# Comparator_HighSpeed.net
KiCad netlist of a schematic drawn in Altium Designer
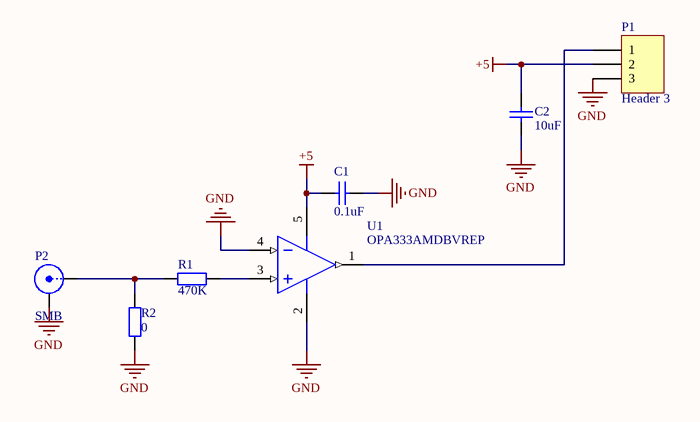
[diagram p0: Comparator_HighSpeed.SchDoc]

(export (version "E")
  (design (tool "Eeschema 10.0.6"))
  (components
    (comp (ref "C1")
      (value "0.1uF")
      (footprint "C0805")
      (description "Capacitor (Semiconductor SIM Model)")
      (fields (field (name "Comment") "Cap Semi") (field (name "PUBLISHER") "Altium Limited"))
      (libsource (lib "Miscellaneous Devices") (part "Cap Semi"))
    )
    (comp (ref "C2")
      (value "10uF")
      (footprint "C0805")
      (description "Capacitor (Semiconductor SIM Model)")
      (fields (field (name "Comment") "Cap Semi") (field (name "PUBLISHER") "Altium Limited"))
      (libsource (lib "Miscellaneous Devices") (part "Cap Semi"))
    )
    (comp (ref "P1")
      (value "Header 3")
      (footprint "HDR1X3")
      (description "Header, 3-Pin")
      (fields (field (name "PUBLISHER") "Altium Limited"))
      (libsource (lib "Miscellaneous Connectors") (part "Header 3"))
    )
    (comp (ref "P2")
      (value "SMB")
      (footprint "SMB_V-RJ45")
      (description "SMB Straight Connector")
      (fields (field (name "PUBLISHER") "Altium Limited"))
      (libsource (lib "Miscellaneous Connectors") (part "SMB"))
    )
    (comp (ref "R1")
      (value "470K")
      (footprint "C0805")
      (description "Resistor")
      (fields (field (name "Comment") "Res2") (field (name "PUBLISHER") "Altium Limited"))
      (libsource (lib "") (part "Res2_1"))
    )
    (comp (ref "R2")
      (value "0")
      (footprint "C0805")
      (description "Resistor")
      (fields (field (name "Comment") "Res2") (field (name "PUBLISHER") "Altium Limited"))
      (libsource (lib "Miscellaneous Devices") (part "Res2"))
    )
    (comp (ref "U1")
      (value "OPA333AMDBVREP")
      (footprint "TI-DBV5_N")
      (fields (field (name "MANUFACTURER") "Texas Instruments"))
      (libsource (lib "TI Amplifiers and Linear Operational Amplifier General Purpose") (part "OPA333AMDBVREP"))
    )
  )
  (nets
    (net (code "1") (name "+5") (class "Default")
      (node (ref "C1") (pin "1") (pinfunction "1_1") (pintype "passive"))
      (node (ref "C2") (pin "2") (pinfunction "2_2") (pintype "passive"))
      (node (ref "P1") (pin "2") (pinfunction "2_2") (pintype "passive"))
      (node (ref "U1") (pin "5") (pinfunction "V+_5") (pintype "power_in"))
    )
    (net (code "2") (name "GND") (class "Default")
      (node (ref "C1") (pin "2") (pinfunction "2_2") (pintype "passive"))
      (node (ref "C2") (pin "1") (pinfunction "1_1") (pintype "passive"))
      (node (ref "P1") (pin "3") (pinfunction "3_3") (pintype "passive"))
      (node (ref "P2") (pin "2") (pinfunction "Y_2") (pintype "passive"))
      (node (ref "R2") (pin "1") (pinfunction "1_1") (pintype "passive"))
      (node (ref "U1") (pin "2") (pinfunction "V-_2") (pintype "power_in"))
      (node (ref "U1") (pin "4") (pinfunction "IN-_4") (pintype "input"))
    )
    (net (code "3") (name "Net-(P2-X)") (class "Default")
      (node (ref "P2") (pin "1") (pinfunction "X_1") (pintype "passive"))
      (node (ref "R1") (pin "1") (pinfunction "1_1") (pintype "passive"))
      (node (ref "R2") (pin "2") (pinfunction "2_2") (pintype "passive"))
    )
    (net (code "4") (name "Net-(U1-IN+)") (class "Default")
      (node (ref "R1") (pin "2") (pinfunction "2_2") (pintype "passive"))
      (node (ref "U1") (pin "3") (pinfunction "IN+_3") (pintype "input"))
    )
    (net (code "5") (name "Net-(U1-OUT)") (class "Default")
      (node (ref "P1") (pin "1") (pinfunction "1_1") (pintype "passive"))
      (node (ref "U1") (pin "1") (pinfunction "OUT_1") (pintype "output"))
    )
  )
)
